# 2017_Carte_RUSH.net
KiCad netlist of a schematic drawn in Altium Designer
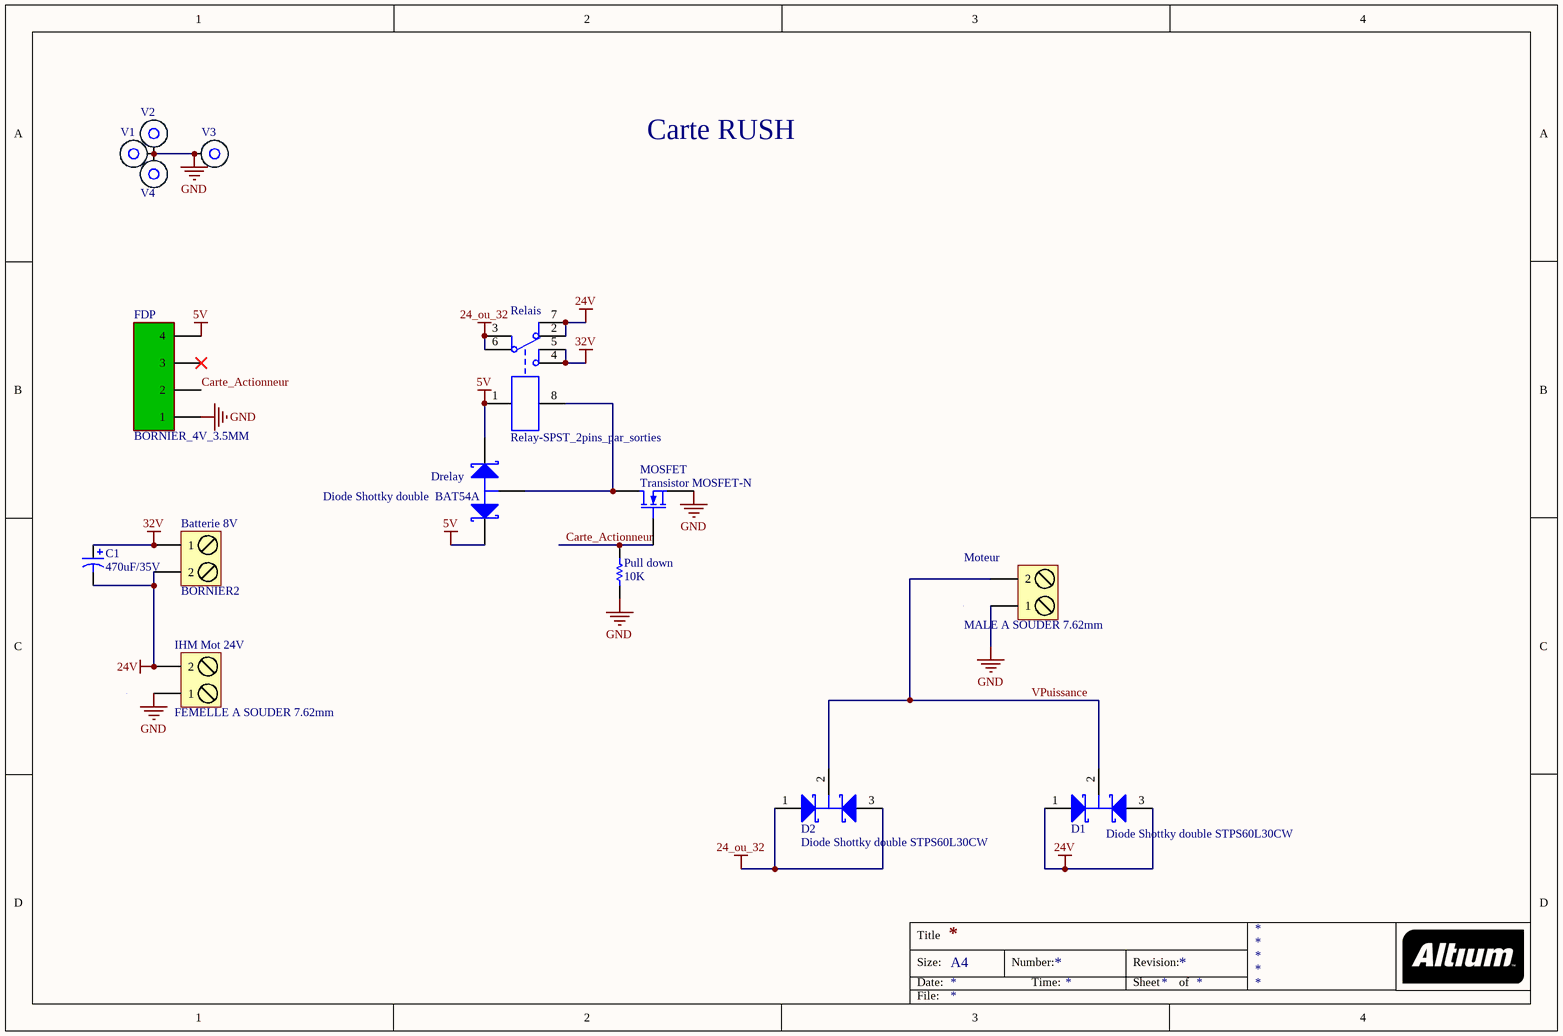
[diagram p0: 2017_Carte_RUSH.SchDoc]

(export (version "E")
  (design (tool "Eeschema 10.0.6"))
  (components
    (comp (ref "Batterie 8V")
      (value "BORNIER2")
      (footprint "BORNIER_2V_5.08MM")
      (description "Terminal blocks, 2 pins, pitch=5mm")
      (libsource (lib "") (part "BORNIER2_1"))
    )
    (comp (ref "C1")
      (value "470uF/35V")
      (footprint "C_10.3mm_G")
      (description "Polarized Capacitor")
      (fields (field (name "PUBLISHER") "Altium Limited"))
      (libsource (lib "_ROBOT") (part "Condensateur Polarise CMS"))
    )
    (comp (ref "D1")
      (value "Diode Shottky double STPS60L30CW")
      (footprint "TO247")
      (description "DIODE SCHOTTKY DOUBLE")
      (fields (field (name "MANUFACTURER PART NUMBER") "BAT54C") (field (name "MANUFACTURER") "ZETEX"))
      (libsource (lib "_ROBOT") (part "Diode Shottky double STPS60L30CW"))
    )
    (comp (ref "D2")
      (value "Diode Shottky double STPS60L30CW")
      (footprint "TO247")
      (description "DIODE SCHOTTKY DOUBLE")
      (fields (field (name "MANUFACTURER PART NUMBER") "BAT54C") (field (name "MANUFACTURER") "ZETEX"))
      (libsource (lib "_ROBOT") (part "Diode Shottky double STPS60L30CW"))
    )
    (comp (ref "Drelay")
      (value "Diode Shottky double  BAT54A")
      (footprint "SOT23-3N")
      (description "DIODE SCHOTTKY DOUBLE")
      (fields (field (name "MANUFACTURER PART NUMBER") "BAT54A") (field (name "MANUFACTURER") "ZETEX"))
      (libsource (lib "_ROBOT") (part "Diode Shottky double  BAT54A"))
    )
    (comp (ref "FDP")
      (value "BORNIER_4V_3.5MM")
      (footprint "BORNIER_4V_3.5MM")
      (libsource (lib "Connecteur") (part "BORNIER_4V_3.5MM"))
    )
    (comp (ref "IHM Mot 24V")
      (value "FEMELLE A SOUDER 7.62mm")
      (footprint "BORNIER2_FEM_COUDE")
      (description "Terminal blocks, 2 pins, pitch=5mm")
      (libsource (lib "Connecteur") (part "BORNIER2"))
    )
    (comp (ref "MOSFET")
      (value "Transistor MOSFET-N")
      (footprint "SOT23-3N")
      (description "N-Channel MOSFET")
      (fields (field (name "PUBLISHER") "Altium Limited"))
      (libsource (lib "_ROBOT") (part "Transistor MOSFET-N"))
    )
    (comp (ref "Moteur")
      (value "MALE A SOUDER 7.62mm")
      (footprint "BORNIER2_FEM_HORIZ")
      (description "Terminal blocks, 2 pins, pitch=5mm")
      (libsource (lib "Connecteur") (part "BORNIER2"))
    )
    (comp (ref "Pull down")
      (value "10K")
      (footprint "R1206_N")
      (description "Resistor")
      (fields (field (name "PUBLISHER") "Altium Limited"))
      (libsource (lib "_ROBOT") (part "Resistor"))
    )
    (comp (ref "Relais")
      (value "Relay-SPST_2pins_par_sorties")
      (footprint "RELAY_TECONNECTIVITY")
      (description "OZ-SS-105LM1,200 - Single-Pole Single-Throw Relay")
      (fields (field (name "PUBLISHER") "Altium Limited"))
      (libsource (lib "_ROBOT") (part "Relay-SPST_2pins_par_sorties"))
    )
    (comp (ref "V1")
      (value "~")
      (footprint "ENTRETOISE_CMS")
      (description "Entretoise Wurth")
      (fields (field (name "PUBLISHER") "Damien Guitton"))
      (libsource (lib "_ROBOT") (part "Entretoise WURTH CMS"))
    )
    (comp (ref "V2")
      (value "~")
      (footprint "ENTRETOISE_CMS")
      (description "Entretoise Wurth")
      (fields (field (name "PUBLISHER") "Damien Guitton"))
      (libsource (lib "_ROBOT") (part "Entretoise WURTH CMS"))
    )
    (comp (ref "V3")
      (value "~")
      (footprint "ENTRETOISE_CMS")
      (description "Entretoise Wurth")
      (fields (field (name "PUBLISHER") "Damien Guitton"))
      (libsource (lib "_ROBOT") (part "Entretoise WURTH CMS"))
    )
    (comp (ref "V4")
      (value "~")
      (footprint "ENTRETOISE_CMS")
      (description "Entretoise Wurth")
      (fields (field (name "PUBLISHER") "Damien Guitton"))
      (libsource (lib "_ROBOT") (part "Entretoise WURTH CMS"))
    )
  )
  (nets
    (net (code "1") (name "/Carte_Actionneur") (class "Default")
      (node (ref "FDP") (pin "2") (pinfunction "2_2") (pintype "passive"))
      (node (ref "MOSFET") (pin "1") (pinfunction "G_1") (pintype "passive"))
      (node (ref "Pull down") (pin "2") (pinfunction "2_2") (pintype "passive"))
    )
    (net (code "2") (name "/VPuissance") (class "Default")
      (node (ref "D1") (pin "2") (pinfunction "K_2") (pintype "passive"))
      (node (ref "D2") (pin "2") (pinfunction "K_2") (pintype "passive"))
      (node (ref "Moteur") (pin "2") (pinfunction "2_2") (pintype "passive"))
    )
    (net (code "3") (name "5V") (class "Default")
      (node (ref "Drelay") (pin "1") (pinfunction "K1_1") (pintype "passive"))
      (node (ref "Drelay") (pin "2") (pinfunction "K2_2") (pintype "passive"))
      (node (ref "FDP") (pin "4") (pinfunction "4_4") (pintype "passive"))
      (node (ref "Relais") (pin "1") (pinfunction "1_1") (pintype "passive"))
    )
    (net (code "4") (name "24V") (class "Default")
      (node (ref "Batterie 8V") (pin "2") (pinfunction "2_2") (pintype "passive"))
      (node (ref "C1") (pin "2") (pinfunction "2_2") (pintype "passive"))
      (node (ref "D1") (pin "1") (pinfunction "A1_1") (pintype "passive"))
      (node (ref "D1") (pin "3") (pinfunction "A2_3") (pintype "passive"))
      (node (ref "IHM Mot 24V") (pin "2") (pinfunction "2_2") (pintype "passive"))
      (node (ref "Relais") (pin "2") (pinfunction "2_2") (pintype "passive"))
      (node (ref "Relais") (pin "7") (pinfunction "7_7") (pintype "passive"))
    )
    (net (code "5") (name "24_ou_32") (class "Default")
      (node (ref "D2") (pin "1") (pinfunction "A1_1") (pintype "passive"))
      (node (ref "D2") (pin "3") (pinfunction "A2_3") (pintype "passive"))
      (node (ref "Relais") (pin "3") (pinfunction "3_3") (pintype "passive"))
      (node (ref "Relais") (pin "6") (pinfunction "6_6") (pintype "passive"))
    )
    (net (code "6") (name "32V") (class "Default")
      (node (ref "Batterie 8V") (pin "1") (pinfunction "1_1") (pintype "passive"))
      (node (ref "C1") (pin "1") (pinfunction "1_1") (pintype "passive"))
      (node (ref "Relais") (pin "4") (pinfunction "4_4") (pintype "passive"))
      (node (ref "Relais") (pin "5") (pinfunction "5_5") (pintype "passive"))
    )
    (net (code "7") (name "GND") (class "Default")
      (node (ref "FDP") (pin "1") (pinfunction "1_1") (pintype "passive"))
      (node (ref "IHM Mot 24V") (pin "1") (pinfunction "1_1") (pintype "passive"))
      (node (ref "MOSFET") (pin "2") (pinfunction "S_2") (pintype "passive"))
      (node (ref "Moteur") (pin "1") (pinfunction "1_1") (pintype "passive"))
      (node (ref "Pull down") (pin "1") (pinfunction "1_1") (pintype "passive"))
      (node (ref "V1") (pin "1") (pinfunction "1_1") (pintype "passive"))
      (node (ref "V2") (pin "1") (pinfunction "1_1") (pintype "passive"))
      (node (ref "V3") (pin "1") (pinfunction "1_1") (pintype "passive"))
      (node (ref "V4") (pin "1") (pinfunction "1_1") (pintype "passive"))
    )
    (net (code "8") (name "Net-(Drelay-A)") (class "Default")
      (node (ref "Drelay") (pin "3") (pinfunction "A_3") (pintype "passive"))
      (node (ref "MOSFET") (pin "3") (pinfunction "D_3") (pintype "passive"))
      (node (ref "Relais") (pin "8") (pinfunction "8_8") (pintype "passive"))
    )
    (net (code "9") (name "unconnected-(FDP-Pad3)") (class "Default")
      (node (ref "FDP") (pin "3") (pinfunction "3_3") (pintype "passive+no_connect"))
    )
  )
)
